# RA08B.net
KiCad netlist of a schematic drawn in Altium Designer
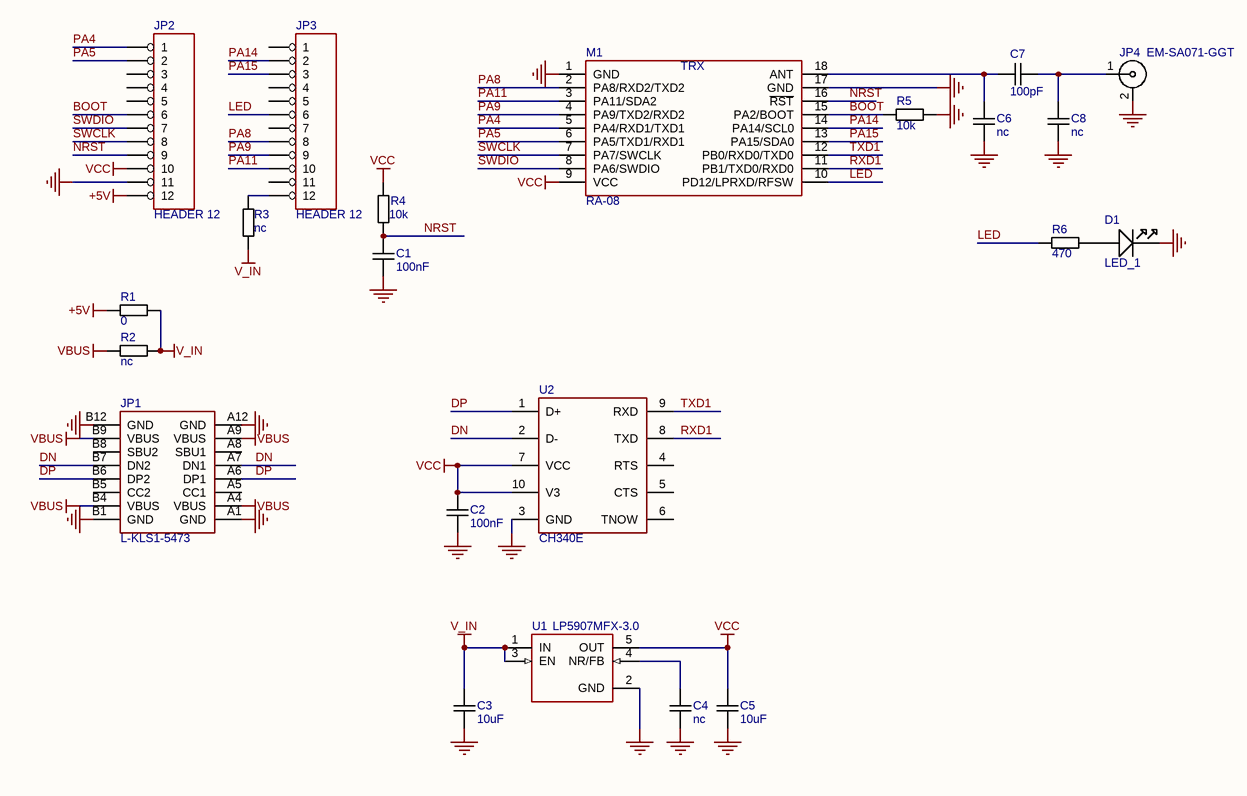
[diagram p0: RA08B.SchDoc]

(export (version "E")
  (design (tool "Eeschema 10.0.6"))
  (components
    (comp (ref "C1")
      (value "100nF")
      (footprint "C-0603")
      (fields (field (name "VOLTAGE") "50V"))
      (libsource (lib "Passive") (part "CAPN"))
    )
    (comp (ref "C2")
      (value "100nF")
      (footprint "C-0603")
      (fields (field (name "VOLTAGE") "50V"))
      (libsource (lib "Passive") (part "CAPN"))
    )
    (comp (ref "C3")
      (value "10uF")
      (footprint "C-0805")
      (fields (field (name "VOLTAGE") "50V"))
      (libsource (lib "Passive") (part "CAPN"))
    )
    (comp (ref "C4")
      (value "nc")
      (footprint "C-0603")
      (fields (field (name "VOLTAGE") "50V"))
      (libsource (lib "Passive") (part "CAPN"))
    )
    (comp (ref "C5")
      (value "10uF")
      (footprint "C-0805")
      (fields (field (name "VOLTAGE") "50V"))
      (libsource (lib "Passive") (part "CAPN"))
    )
    (comp (ref "C6")
      (value "nc")
      (footprint "C-0603")
      (fields (field (name "VOLTAGE") "50V"))
      (libsource (lib "Passive") (part "CAPN"))
    )
    (comp (ref "C7")
      (value "100pF")
      (footprint "C-0603")
      (fields (field (name "VOLTAGE") "50V"))
      (libsource (lib "Passive") (part "CAPN"))
    )
    (comp (ref "C8")
      (value "nc")
      (footprint "C-0603")
      (fields (field (name "VOLTAGE") "50V"))
      (libsource (lib "Passive") (part "CAPN"))
    )
    (comp (ref "D1") (value "LED_1") (footprint "LED_0805") (libsource (lib "Diodes") (part "LED_1")))
    (comp (ref "JP1")
      (value "L-KLS1-5473")
      (footprint "USB_C_SMD_SLOT")
      (libsource (lib "Connectors") (part "L-KLS1-5473"))
    )
    (comp (ref "JP2")
      (value "HEADER 12")
      (footprint "PLS1-12")
      (libsource (lib "Connectors") (part "HEADER 12"))
    )
    (comp (ref "JP3")
      (value "HEADER 12")
      (footprint "PLS1-12")
      (libsource (lib "Connectors") (part "HEADER 12"))
    )
    (comp (ref "JP4")
      (value "EM-SA071-GGT")
      (footprint "SMA_F_EDGE")
      (description "SMA Female R/A PCB Mount")
      (libsource (lib "Connectors") (part "SMA"))
    )
    (comp (ref "M1") (value "RA-08") (footprint "LGA18_RA08") (libsource (lib "RFmodules") (part "RA-08")))
    (comp (ref "R1") (value "0") (footprint "R-0603") (libsource (lib "Passive") (part "RES")))
    (comp (ref "R2") (value "nc") (footprint "R-0603") (libsource (lib "Passive") (part "RES")))
    (comp (ref "R3") (value "nc") (footprint "R-0603") (libsource (lib "") (part "RES_1")))
    (comp (ref "R4") (value "10k") (footprint "R-0603") (libsource (lib "") (part "RES_1")))
    (comp (ref "R5") (value "10k") (footprint "R-0603") (libsource (lib "") (part "RES_2")))
    (comp (ref "R6") (value "470") (footprint "R-0603") (libsource (lib "") (part "RES_2")))
    (comp (ref "U1")
      (value "LP5907MFX-3.0")
      (footprint "SOT-23-5")
      (description "250mA Low-Dropout Regulator")
      (libsource (lib "ICs") (part "LP5907"))
    )
    (comp (ref "U2") (value "CH340E") (footprint "MSOP-10") (libsource (lib "ICs") (part "CH340E")))
  )
  (nets
    (net (code "1") (name "+5V") (class "Default")
      (node (ref "JP2") (pin "12") (pinfunction "12_12") (pintype "passive"))
      (node (ref "R1") (pin "1") (pinfunction "1_1") (pintype "passive"))
    )
    (net (code "2") (name "/BOOT") (class "Default")
      (node (ref "JP2") (pin "6") (pinfunction "6_6") (pintype "passive"))
      (node (ref "M1") (pin "15") (pinfunction "PA2/BOOT_15") (pintype "passive"))
      (node (ref "R5") (pin "2") (pinfunction "2_2") (pintype "passive"))
    )
    (net (code "3") (name "/DN") (class "Default")
      (node (ref "JP1") (pin "A7") (pinfunction "DN1_A7") (pintype "passive"))
      (node (ref "JP1") (pin "B7") (pinfunction "DN2_B7") (pintype "passive"))
      (node (ref "U2") (pin "2") (pinfunction "D-_2") (pintype "passive"))
    )
    (net (code "4") (name "/DP") (class "Default")
      (node (ref "JP1") (pin "A6") (pinfunction "DP1_A6") (pintype "passive"))
      (node (ref "JP1") (pin "B6") (pinfunction "DP2_B6") (pintype "passive"))
      (node (ref "U2") (pin "1") (pinfunction "D+_1") (pintype "passive"))
    )
    (net (code "5") (name "/LED") (class "Default")
      (node (ref "JP3") (pin "6") (pinfunction "6_6") (pintype "passive"))
      (node (ref "M1") (pin "10") (pinfunction "PD12/LPRXD/RFSW_10") (pintype "passive"))
      (node (ref "R6") (pin "2") (pinfunction "2_2") (pintype "passive"))
    )
    (net (code "6") (name "/NRST") (class "Default")
      (node (ref "C1") (pin "2") (pinfunction "2_2") (pintype "passive"))
      (node (ref "JP2") (pin "9") (pinfunction "9_9") (pintype "passive"))
      (node (ref "M1") (pin "16") (pinfunction "~{RST}_16") (pintype "passive"))
      (node (ref "R4") (pin "1") (pinfunction "1_1") (pintype "passive"))
    )
    (net (code "7") (name "/PA4") (class "Default")
      (node (ref "JP2") (pin "1") (pinfunction "1_1") (pintype "passive"))
      (node (ref "M1") (pin "5") (pinfunction "PA4/RXD1/TXD1_5") (pintype "passive"))
    )
    (net (code "8") (name "/PA5") (class "Default")
      (node (ref "JP2") (pin "2") (pinfunction "2_2") (pintype "passive"))
      (node (ref "M1") (pin "6") (pinfunction "PA5/TXD1/RXD1_6") (pintype "passive"))
    )
    (net (code "9") (name "/PA8") (class "Default")
      (node (ref "JP3") (pin "8") (pinfunction "8_8") (pintype "passive"))
      (node (ref "M1") (pin "2") (pinfunction "PA8/RXD2/TXD2_2") (pintype "passive"))
    )
    (net (code "10") (name "/PA9") (class "Default")
      (node (ref "JP3") (pin "9") (pinfunction "9_9") (pintype "passive"))
      (node (ref "M1") (pin "4") (pinfunction "PA9/TXD2/RXD2_4") (pintype "passive"))
    )
    (net (code "11") (name "/PA11") (class "Default")
      (node (ref "JP3") (pin "10") (pinfunction "10_10") (pintype "passive"))
      (node (ref "M1") (pin "3") (pinfunction "PA11/SDA2_3") (pintype "passive"))
    )
    (net (code "12") (name "/PA14") (class "Default")
      (node (ref "JP3") (pin "2") (pinfunction "2_2") (pintype "passive"))
      (node (ref "M1") (pin "14") (pinfunction "PA14/SCL0_14") (pintype "passive"))
    )
    (net (code "13") (name "/PA15") (class "Default")
      (node (ref "JP3") (pin "3") (pinfunction "3_3") (pintype "passive"))
      (node (ref "M1") (pin "13") (pinfunction "PA15/SDA0_13") (pintype "passive"))
    )
    (net (code "14") (name "/RXD1") (class "Default")
      (node (ref "M1") (pin "11") (pinfunction "PB1/TXD0/RXD0_11") (pintype "passive"))
      (node (ref "U2") (pin "8") (pinfunction "TXD_8") (pintype "passive"))
    )
    (net (code "15") (name "/SWCLK") (class "Default")
      (node (ref "JP2") (pin "8") (pinfunction "8_8") (pintype "passive"))
      (node (ref "M1") (pin "7") (pinfunction "PA7/SWCLK_7") (pintype "passive"))
    )
    (net (code "16") (name "/SWDIO") (class "Default")
      (node (ref "JP2") (pin "7") (pinfunction "7_7") (pintype "passive"))
      (node (ref "M1") (pin "8") (pinfunction "PA6/SWDIO_8") (pintype "passive"))
    )
    (net (code "17") (name "/TXD1") (class "Default")
      (node (ref "M1") (pin "12") (pinfunction "PB0/RXD0/TXD0_12") (pintype "passive"))
      (node (ref "U2") (pin "9") (pinfunction "RXD_9") (pintype "passive"))
    )
    (net (code "18") (name "GND") (class "Default")
      (node (ref "C1") (pin "1") (pinfunction "1_1") (pintype "passive"))
      (node (ref "C2") (pin "1") (pinfunction "1_1") (pintype "passive"))
      (node (ref "C3") (pin "2") (pinfunction "2_2") (pintype "passive"))
      (node (ref "C4") (pin "2") (pinfunction "2_2") (pintype "passive"))
      (node (ref "C5") (pin "2") (pinfunction "2_2") (pintype "passive"))
      (node (ref "C6") (pin "1") (pinfunction "1_1") (pintype "passive"))
      (node (ref "C8") (pin "1") (pinfunction "1_1") (pintype "passive"))
      (node (ref "D1") (pin "K") (pinfunction "CATHODE_K") (pintype "passive"))
      (node (ref "JP1") (pin "A1") (pinfunction "GND_A1") (pintype "passive"))
      (node (ref "JP1") (pin "A12") (pinfunction "GND_A12") (pintype "passive"))
      (node (ref "JP1") (pin "B1") (pinfunction "GND_B1") (pintype "passive"))
      (node (ref "JP1") (pin "B12") (pinfunction "GND_B12") (pintype "passive"))
      (node (ref "JP2") (pin "11") (pinfunction "11_11") (pintype "passive"))
      (node (ref "JP4") (pin "2") (pinfunction "2_2") (pintype "passive"))
      (node (ref "M1") (pin "1") (pinfunction "GND_1") (pintype "passive"))
      (node (ref "M1") (pin "17") (pinfunction "GND_17") (pintype "passive"))
      (node (ref "R5") (pin "1") (pinfunction "1_1") (pintype "passive"))
      (node (ref "U1") (pin "2") (pinfunction "GND_2") (pintype "power_in"))
      (node (ref "U2") (pin "3") (pinfunction "GND_3") (pintype "passive"))
    )
    (net (code "19") (name "Net-(C7-Pad2)") (class "Default")
      (node (ref "C7") (pin "2") (pinfunction "2_2") (pintype "passive"))
      (node (ref "C8") (pin "2") (pinfunction "2_2") (pintype "passive"))
      (node (ref "JP4") (pin "1") (pinfunction "1_1") (pintype "passive"))
    )
    (net (code "20") (name "Net-(D1-ANODE)") (class "Default")
      (node (ref "D1") (pin "A") (pinfunction "ANODE_A") (pintype "passive"))
      (node (ref "R6") (pin "1") (pinfunction "1_1") (pintype "passive"))
    )
    (net (code "21") (name "Net-(JP3-Pad12)") (class "Default")
      (node (ref "JP3") (pin "12") (pinfunction "12_12") (pintype "passive"))
      (node (ref "R3") (pin "2") (pinfunction "2_2") (pintype "passive"))
    )
    (net (code "22") (name "Net-(M1-ANT)") (class "Default")
      (node (ref "C6") (pin "2") (pinfunction "2_2") (pintype "passive"))
      (node (ref "C7") (pin "1") (pinfunction "1_1") (pintype "passive"))
      (node (ref "M1") (pin "18") (pinfunction "ANT_18") (pintype "passive"))
    )
    (net (code "23") (name "Net-(U1-NR{slash}FB)") (class "Default")
      (node (ref "C4") (pin "1") (pinfunction "1_1") (pintype "passive"))
      (node (ref "U1") (pin "4") (pinfunction "NR/FB_4") (pintype "input"))
    )
    (net (code "24") (name "VBUS") (class "Default")
      (node (ref "JP1") (pin "A4") (pinfunction "VBUS_A4") (pintype "passive"))
      (node (ref "JP1") (pin "A9") (pinfunction "VBUS_A9") (pintype "passive"))
      (node (ref "JP1") (pin "B4") (pinfunction "VBUS_B4") (pintype "passive"))
      (node (ref "JP1") (pin "B9") (pinfunction "VBUS_B9") (pintype "passive"))
      (node (ref "R2") (pin "1") (pinfunction "1_1") (pintype "passive"))
    )
    (net (code "25") (name "VCC") (class "Default")
      (node (ref "C2") (pin "2") (pinfunction "2_2") (pintype "passive"))
      (node (ref "C5") (pin "1") (pinfunction "1_1") (pintype "passive"))
      (node (ref "JP2") (pin "10") (pinfunction "10_10") (pintype "passive"))
      (node (ref "M1") (pin "9") (pinfunction "VCC_9") (pintype "passive"))
      (node (ref "R4") (pin "2") (pinfunction "2_2") (pintype "passive"))
      (node (ref "U1") (pin "5") (pinfunction "OUT_5") (pintype "power_in"))
      (node (ref "U2") (pin "10") (pinfunction "V3_10") (pintype "passive"))
      (node (ref "U2") (pin "7") (pinfunction "VCC_7") (pintype "passive"))
    )
    (net (code "26") (name "VSS") (class "Default")
      (node (ref "JP1") (pin "17") (pinfunction "VSS_17") (pintype "power_in"))
    )
    (net (code "27") (name "V_IN") (class "Default")
      (node (ref "C3") (pin "1") (pinfunction "1_1") (pintype "passive"))
      (node (ref "R1") (pin "2") (pinfunction "2_2") (pintype "passive"))
      (node (ref "R2") (pin "2") (pinfunction "2_2") (pintype "passive"))
      (node (ref "R3") (pin "1") (pinfunction "1_1") (pintype "passive"))
      (node (ref "U1") (pin "1") (pinfunction "IN_1") (pintype "power_in"))
      (node (ref "U1") (pin "3") (pinfunction "EN_3") (pintype "input"))
    )
    (net (code "28") (name "unconnected-(JP1-CC1-PadA5)") (class "Default")
      (node (ref "JP1") (pin "A5") (pinfunction "CC1_A5") (pintype "passive"))
    )
    (net (code "29") (name "unconnected-(JP1-CC2-PadB5)") (class "Default")
      (node (ref "JP1") (pin "B5") (pinfunction "CC2_B5") (pintype "passive"))
    )
    (net (code "30") (name "unconnected-(JP1-SBU1-PadA8)") (class "Default")
      (node (ref "JP1") (pin "A8") (pinfunction "SBU1_A8") (pintype "passive"))
    )
    (net (code "31") (name "unconnected-(JP1-SBU2-PadB8)") (class "Default")
      (node (ref "JP1") (pin "B8") (pinfunction "SBU2_B8") (pintype "passive"))
    )
    (net (code "32") (name "unconnected-(JP2-Pad3)") (class "Default")
      (node (ref "JP2") (pin "3") (pinfunction "3_3") (pintype "passive"))
    )
    (net (code "33") (name "unconnected-(JP2-Pad4)") (class "Default")
      (node (ref "JP2") (pin "4") (pinfunction "4_4") (pintype "passive"))
    )
    (net (code "34") (name "unconnected-(JP2-Pad5)") (class "Default")
      (node (ref "JP2") (pin "5") (pinfunction "5_5") (pintype "passive"))
    )
    (net (code "35") (name "unconnected-(JP3-Pad1)") (class "Default")
      (node (ref "JP3") (pin "1") (pinfunction "1_1") (pintype "passive"))
    )
    (net (code "36") (name "unconnected-(JP3-Pad4)") (class "Default")
      (node (ref "JP3") (pin "4") (pinfunction "4_4") (pintype "passive"))
    )
    (net (code "37") (name "unconnected-(JP3-Pad5)") (class "Default")
      (node (ref "JP3") (pin "5") (pinfunction "5_5") (pintype "passive"))
    )
    (net (code "38") (name "unconnected-(JP3-Pad7)") (class "Default")
      (node (ref "JP3") (pin "7") (pinfunction "7_7") (pintype "passive"))
    )
    (net (code "39") (name "unconnected-(JP3-Pad11)") (class "Default")
      (node (ref "JP3") (pin "11") (pinfunction "11_11") (pintype "passive"))
    )
    (net (code "40") (name "unconnected-(U2-CTS-Pad5)") (class "Default")
      (node (ref "U2") (pin "5") (pinfunction "CTS_5") (pintype "passive"))
    )
    (net (code "41") (name "unconnected-(U2-RTS-Pad4)") (class "Default")
      (node (ref "U2") (pin "4") (pinfunction "RTS_4") (pintype "passive"))
    )
    (net (code "42") (name "unconnected-(U2-TNOW-Pad6)") (class "Default")
      (node (ref "U2") (pin "6") (pinfunction "TNOW_6") (pintype "passive"))
    )
  )
)
